# design.net
KiCad netlist of a schematic drawn in Altium Designer
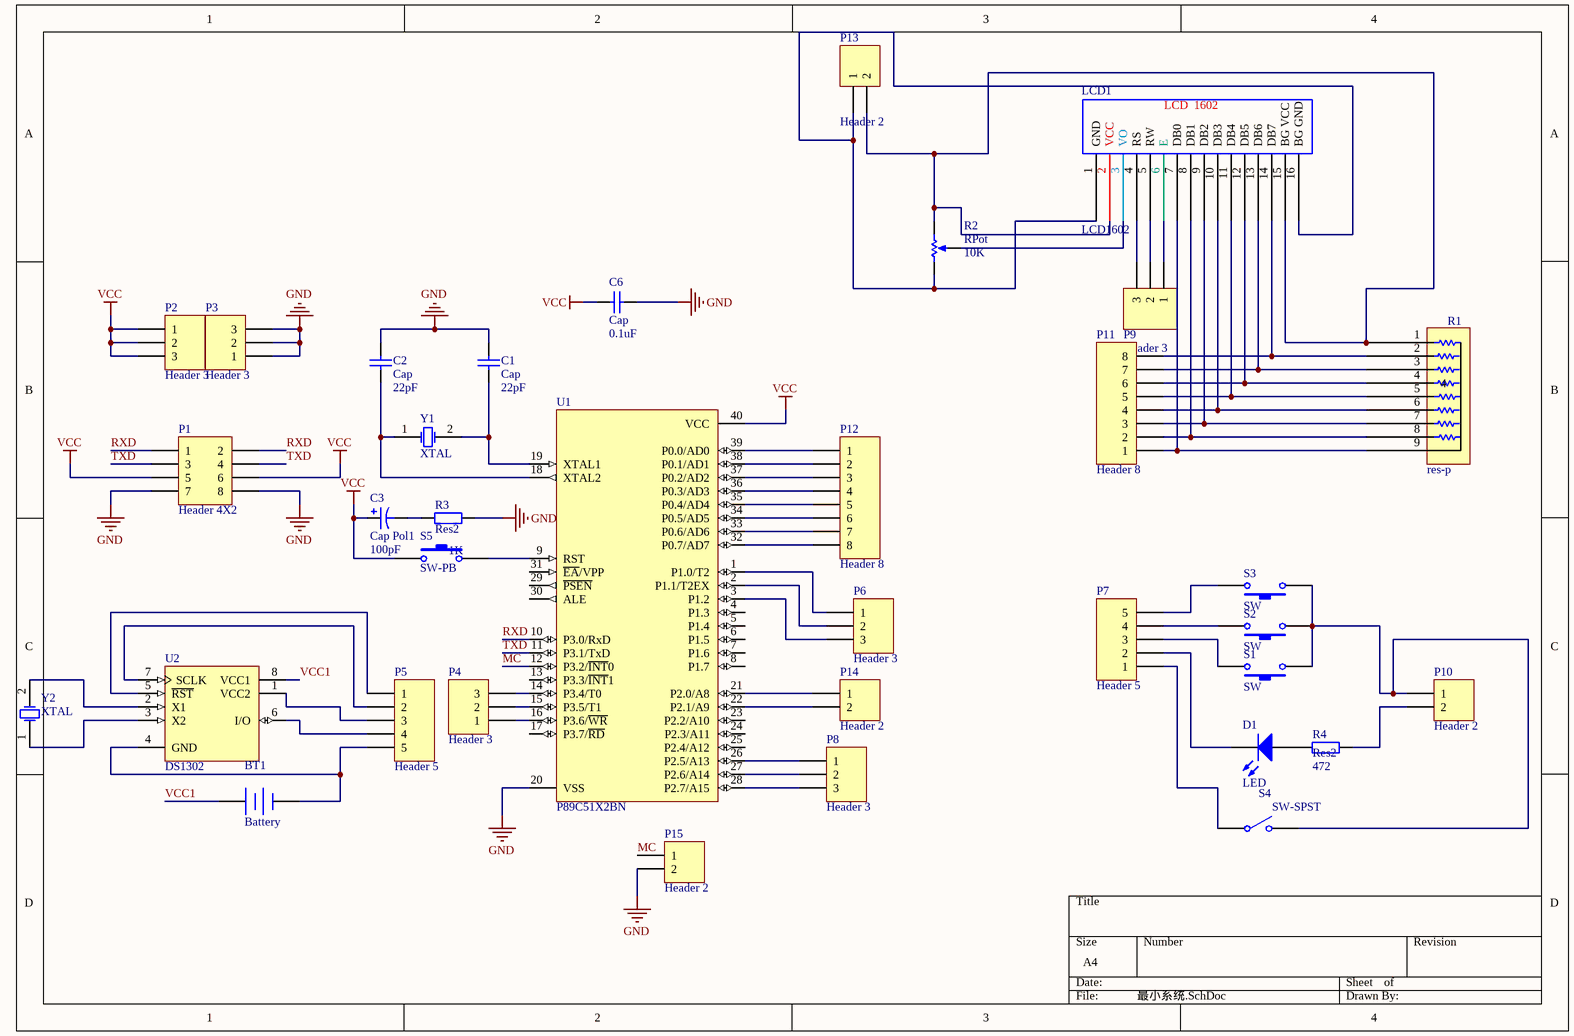
[diagram p0: 最小系统.SchDoc]

(export (version "E")
  (design (tool "Eeschema 10.0.6"))
  (components
    (comp (ref "BT1")
      (value "Battery")
      (footprint "BAT-2")
      (description "Multicell Battery")
      (fields (field (name "PUBLISHER") "Altium Limited"))
      (libsource (lib "Miscellaneous Devices") (part "Battery"))
    )
    (comp (ref "C1")
      (value "Cap")
      (footprint "CAPR2.54-5.1x3.2")
      (description "Capacitor")
      (fields (field (name "ALTIUM_VALUE") "22pF") (field (name "PUBLISHER") "Altium Limited"))
      (libsource (lib "Miscellaneous Devices") (part "Cap"))
    )
    (comp (ref "C2")
      (value "Cap")
      (footprint "CAPR2.54-5.1x3.2")
      (description "Capacitor")
      (fields (field (name "ALTIUM_VALUE") "22pF") (field (name "PUBLISHER") "Altium Limited"))
      (libsource (lib "Miscellaneous Devices") (part "Cap"))
    )
    (comp (ref "C3")
      (value "Cap Pol1")
      (footprint "CAPPR1.27-1.7x2.8")
      (description "Polarized Capacitor (Radial)")
      (fields (field (name "ALTIUM_VALUE") "100pF") (field (name "PUBLISHER") "Altium Limited"))
      (libsource (lib "Miscellaneous Devices") (part "Cap Pol1"))
    )
    (comp (ref "C6")
      (value "Cap")
      (footprint "RAD-0.3")
      (description "Capacitor")
      (fields (field (name "ALTIUM_VALUE") "0.1uF") (field (name "PUBLISHER") "Altium Limited"))
      (libsource (lib "Miscellaneous Devices") (part "Cap"))
    )
    (comp (ref "D1") (value "LED") (footprint "LED-1") (libsource (lib "我的集成库库") (part "LED")))
    (comp (ref "LCD1") (value "LCD1602") (footprint "1602LCD") (libsource (lib "MyInt_Lib") (part "LCD1602")))
    (comp (ref "P1")
      (value "Header 4X2")
      (footprint "HDR2X4")
      (description "Header, 4-Pin, Dual row")
      (fields (field (name "PUBLISHER") "Altium Limited"))
      (libsource (lib "Miscellaneous Connectors") (part "Header 4X2"))
    )
    (comp (ref "P2")
      (value "Header 3")
      (footprint "HDR1X3")
      (description "Header, 3-Pin")
      (fields (field (name "PUBLISHER") "Altium Limited"))
      (libsource (lib "Miscellaneous Connectors") (part "Header 3"))
    )
    (comp (ref "P3")
      (value "Header 3")
      (footprint "HDR1X3")
      (description "Header, 3-Pin")
      (fields (field (name "PUBLISHER") "Altium Limited"))
      (libsource (lib "") (part "Header 3_1"))
    )
    (comp (ref "P4")
      (value "Header 3")
      (footprint "HDR1X3")
      (description "Header, 3-Pin")
      (fields (field (name "PUBLISHER") "Altium Limited"))
      (libsource (lib "") (part "Header 3_1"))
    )
    (comp (ref "P5")
      (value "Header 5")
      (footprint "HDR1X5")
      (description "Header, 5-Pin")
      (fields (field (name "PUBLISHER") "Altium Limited"))
      (libsource (lib "") (part "Header 5_1"))
    )
    (comp (ref "P6")
      (value "Header 3")
      (footprint "HDR1X3")
      (description "Header, 3-Pin")
      (fields (field (name "PUBLISHER") "Altium Limited"))
      (libsource (lib "Miscellaneous Connectors") (part "Header 3"))
    )
    (comp (ref "P7")
      (value "Header 5")
      (footprint "HDR1X5")
      (description "Header, 5-Pin")
      (fields (field (name "PUBLISHER") "Altium Limited"))
      (libsource (lib "Miscellaneous Connectors") (part "Header 5"))
    )
    (comp (ref "P8")
      (value "Header 3")
      (footprint "HDR1X3")
      (description "Header, 3-Pin")
      (fields (field (name "PUBLISHER") "Altium Limited"))
      (libsource (lib "Miscellaneous Connectors") (part "Header 3"))
    )
    (comp (ref "P9")
      (value "Header 3")
      (footprint "HDR1X3")
      (description "Header, 3-Pin")
      (fields (field (name "PUBLISHER") "Altium Limited"))
      (libsource (lib "") (part "Header 3_2"))
    )
    (comp (ref "P10")
      (value "Header 2")
      (footprint "HDR1X2")
      (description "Header, 2-Pin")
      (fields (field (name "PUBLISHER") "Altium Limited"))
      (libsource (lib "") (part "Header 2_1"))
    )
    (comp (ref "P11")
      (value "Header 8")
      (footprint "HDR1X8")
      (description "Header, 8-Pin")
      (fields (field (name "PUBLISHER") "Altium Limited"))
      (libsource (lib "") (part "Header 8_1"))
    )
    (comp (ref "P12")
      (value "Header 8")
      (footprint "HDR1X8")
      (description "Header, 8-Pin")
      (fields (field (name "PUBLISHER") "Altium Limited"))
      (libsource (lib "Miscellaneous Connectors") (part "Header 8"))
    )
    (comp (ref "P13")
      (value "Header 2")
      (footprint "HDR1X2")
      (description "Header, 2-Pin")
      (fields (field (name "PUBLISHER") "Altium Limited"))
      (libsource (lib "Miscellaneous Connectors") (part "Header 2"))
    )
    (comp (ref "P14")
      (value "Header 2")
      (footprint "HDR1X2")
      (description "Header, 2-Pin")
      (fields (field (name "PUBLISHER") "Altium Limited"))
      (libsource (lib "") (part "Header 2_1"))
    )
    (comp (ref "P15")
      (value "Header 2")
      (footprint "HDR1X2")
      (description "Header, 2-Pin")
      (fields (field (name "PUBLISHER") "Altium Limited"))
      (libsource (lib "") (part "Header 2_1"))
    )
    (comp (ref "R1") (value "res-p") (footprint "HDR1X9") (libsource (lib "我的集成库库") (part "res-p")))
    (comp (ref "R2")
      (value "RPot")
      (footprint "VR5")
      (description "Potentiometer")
      (fields (field (name "ALTIUM_VALUE") "10K") (field (name "PUBLISHER") "Altium Limited"))
      (libsource (lib "Miscellaneous Devices") (part "RPot"))
    )
    (comp (ref "R3")
      (value "Res2")
      (footprint "AXIAL-0.4")
      (description "Resistor")
      (fields (field (name "ALTIUM_VALUE") "1K") (field (name "PUBLISHER") "Altium Limited"))
      (libsource (lib "Miscellaneous Devices") (part "Res2"))
    )
    (comp (ref "R4")
      (value "Res2")
      (footprint "AXIAL-0.4")
      (description "Resistor")
      (fields (field (name "ALTIUM_VALUE") "472") (field (name "PUBLISHER") "Altium Limited"))
      (libsource (lib "Miscellaneous Devices") (part "Res2"))
    )
    (comp (ref "S1") (value "SW") (footprint "SW/PB-V4/H7.1") (libsource (lib "我的集成库库") (part "SWITCH")))
    (comp (ref "S2") (value "SW") (footprint "SW/PB-V4/H7.1") (libsource (lib "我的集成库库") (part "SWITCH")))
    (comp (ref "S3") (value "SW") (footprint "SW/PB-V4/H7.1") (libsource (lib "我的集成库库") (part "SWITCH")))
    (comp (ref "S4")
      (value "SW-SPST")
      (footprint "SPST-2")
      (description "Single-Pole, Single-Throw Switch")
      (fields (field (name "PUBLISHER") "Altium Limited"))
      (libsource (lib "Miscellaneous Devices") (part "SW-SPST"))
    )
    (comp (ref "S5")
      (value "SW-PB")
      (footprint "SW/PB-V4/H7.1")
      (description "Switch")
      (fields (field (name "PUBLISHER") "Altium Limited"))
      (libsource (lib "Miscellaneous Devices") (part "SW-PB"))
    )
    (comp (ref "U1")
      (value "P89C51X2BN")
      (footprint "SOT129-1")
      (description "80C51 8-Bit Flash Microcontroller Family, 4 kB Flash")
      (fields (field (name "PUBLISHER") "Altium Limited"))
      (libsource (lib "Philips Microcontroller 8-Bit") (part "P89C51X2BN"))
    )
    (comp (ref "U2")
      (value "DS1302")
      (footprint "DIP8")
      (description "Trickle Charge Timekeeping Chip")
      (fields (field (name "PUBLISHER") "Altium Limited"))
      (libsource (lib "Dallas Peripheral Real Time Clock") (part "DS1302"))
    )
    (comp (ref "Y1")
      (value "XTAL")
      (footprint "BCY-W2/D3.1")
      (description "Crystal Oscillator")
      (fields (field (name "PUBLISHER") "Altium Limited"))
      (libsource (lib "Miscellaneous Devices") (part "XTAL"))
    )
    (comp (ref "Y2")
      (value "XTAL")
      (footprint "BCY-W2/D3.1")
      (description "Crystal Oscillator")
      (fields (field (name "PUBLISHER") "Altium Limited"))
      (libsource (lib "Miscellaneous Devices") (part "XTAL"))
    )
  )
  (nets
    (net (code "1") (name "/MC") (class "Default")
      (node (ref "P15") (pin "1") (pinfunction "1_1") (pintype "passive"))
      (node (ref "U1") (pin "12") (pinfunction "P3.2/~{INT}0_12") (pintype "bidirectional"))
    )
    (net (code "2") (name "/RXD") (class "Default")
      (node (ref "P1") (pin "1") (pinfunction "1_1") (pintype "passive"))
      (node (ref "P1") (pin "2") (pinfunction "2_2") (pintype "passive"))
      (node (ref "U1") (pin "10") (pinfunction "P3.0/RxD_10") (pintype "bidirectional"))
    )
    (net (code "3") (name "/TXD") (class "Default")
      (node (ref "P1") (pin "3") (pinfunction "3_3") (pintype "passive"))
      (node (ref "P1") (pin "4") (pinfunction "4_4") (pintype "passive"))
      (node (ref "U1") (pin "11") (pinfunction "P3.1/TxD_11") (pintype "bidirectional"))
    )
    (net (code "4") (name "/VCC1") (class "Default")
      (node (ref "BT1") (pin "1") (pinfunction "+_1") (pintype "passive"))
      (node (ref "U2") (pin "8") (pinfunction "VCC1_8") (pintype "power_in"))
    )
    (net (code "5") (name "GND") (class "Default")
      (node (ref "C1") (pin "2") (pinfunction "2_2") (pintype "passive"))
      (node (ref "C2") (pin "2") (pinfunction "2_2") (pintype "passive"))
      (node (ref "C6") (pin "2") (pinfunction "2_2") (pintype "passive"))
      (node (ref "P1") (pin "7") (pinfunction "7_7") (pintype "passive"))
      (node (ref "P1") (pin "8") (pinfunction "8_8") (pintype "passive"))
      (node (ref "P15") (pin "2") (pinfunction "2_2") (pintype "passive"))
      (node (ref "P3") (pin "1") (pinfunction "1_1") (pintype "passive"))
      (node (ref "P3") (pin "2") (pinfunction "2_2") (pintype "passive"))
      (node (ref "P3") (pin "3") (pinfunction "3_3") (pintype "passive"))
      (node (ref "R3") (pin "2") (pinfunction "2_2") (pintype "passive"))
      (node (ref "U1") (pin "20") (pinfunction "VSS_20") (pintype "power_in"))
    )
    (net (code "6") (name "Net-(BT1--)") (class "Default")
      (node (ref "BT1") (pin "2") (pinfunction "-_2") (pintype "passive"))
      (node (ref "P5") (pin "5") (pinfunction "5_5") (pintype "passive"))
      (node (ref "U2") (pin "4") (pinfunction "GND_4") (pintype "power_in"))
    )
    (net (code "7") (name "Net-(C3-Pad2)") (class "Default")
      (node (ref "C3") (pin "2") (pinfunction "2_2") (pintype "passive"))
      (node (ref "R3") (pin "1") (pinfunction "1_1") (pintype "passive"))
    )
    (net (code "8") (name "Net-(D1-A)") (class "Default")
      (node (ref "D1") (pin "1") (pinfunction "A_1") (pintype "passive"))
      (node (ref "R4") (pin "1") (pinfunction "1_1") (pintype "passive"))
    )
    (net (code "9") (name "Net-(D1-K)") (class "Default")
      (node (ref "D1") (pin "2") (pinfunction "K_2") (pintype "passive"))
      (node (ref "P7") (pin "2") (pinfunction "2_2") (pintype "passive"))
    )
    (net (code "10") (name "Net-(LCD1-BG_GND)") (class "Default")
      (node (ref "LCD1") (pin "1") (pinfunction "GND_1") (pintype "passive"))
      (node (ref "LCD1") (pin "16") (pinfunction "BG_GND_16") (pintype "passive"))
      (node (ref "P13") (pin "1") (pinfunction "1_1") (pintype "passive"))
      (node (ref "R2") (pin "1") (pinfunction "TOP_1") (pintype "passive"))
    )
    (net (code "11") (name "Net-(LCD1-BG_VCC)") (class "Default")
      (node (ref "LCD1") (pin "15") (pinfunction "BG_VCC_15") (pintype "passive"))
      (node (ref "LCD1") (pin "2") (pinfunction "VCC_2") (pintype "passive"))
      (node (ref "P13") (pin "2") (pinfunction "2_2") (pintype "passive"))
      (node (ref "R1") (pin "1") (pinfunction "1_1") (pintype "passive"))
      (node (ref "R2") (pin "2") (pinfunction "BOT_2") (pintype "passive"))
    )
    (net (code "12") (name "Net-(LCD1-DB0)") (class "Default")
      (node (ref "LCD1") (pin "7") (pinfunction "DB0_7") (pintype "passive"))
      (node (ref "P11") (pin "1") (pinfunction "1_1") (pintype "passive"))
      (node (ref "R1") (pin "9") (pinfunction "9_9") (pintype "passive"))
    )
    (net (code "13") (name "Net-(LCD1-DB1)") (class "Default")
      (node (ref "LCD1") (pin "8") (pinfunction "DB1_8") (pintype "passive"))
      (node (ref "P11") (pin "2") (pinfunction "2_2") (pintype "passive"))
      (node (ref "R1") (pin "8") (pinfunction "8_8") (pintype "passive"))
    )
    (net (code "14") (name "Net-(LCD1-DB2)") (class "Default")
      (node (ref "LCD1") (pin "9") (pinfunction "DB2_9") (pintype "passive"))
      (node (ref "P11") (pin "3") (pinfunction "3_3") (pintype "passive"))
      (node (ref "R1") (pin "7") (pinfunction "7_7") (pintype "passive"))
    )
    (net (code "15") (name "Net-(LCD1-DB3)") (class "Default")
      (node (ref "LCD1") (pin "10") (pinfunction "DB3_10") (pintype "passive"))
      (node (ref "P11") (pin "4") (pinfunction "4_4") (pintype "passive"))
      (node (ref "R1") (pin "6") (pinfunction "6_6") (pintype "passive"))
    )
    (net (code "16") (name "Net-(LCD1-DB4)") (class "Default")
      (node (ref "LCD1") (pin "11") (pinfunction "DB4_11") (pintype "passive"))
      (node (ref "P11") (pin "5") (pinfunction "5_5") (pintype "passive"))
      (node (ref "R1") (pin "5") (pinfunction "5_5") (pintype "passive"))
    )
    (net (code "17") (name "Net-(LCD1-DB5)") (class "Default")
      (node (ref "LCD1") (pin "12") (pinfunction "DB5_12") (pintype "passive"))
      (node (ref "P11") (pin "6") (pinfunction "6_6") (pintype "passive"))
      (node (ref "R1") (pin "4") (pinfunction "4_4") (pintype "passive"))
    )
    (net (code "18") (name "Net-(LCD1-DB6)") (class "Default")
      (node (ref "LCD1") (pin "13") (pinfunction "DB6_13") (pintype "passive"))
      (node (ref "P11") (pin "7") (pinfunction "7_7") (pintype "passive"))
      (node (ref "R1") (pin "3") (pinfunction "3_3") (pintype "passive"))
    )
    (net (code "19") (name "Net-(LCD1-DB7)") (class "Default")
      (node (ref "LCD1") (pin "14") (pinfunction "DB7_14") (pintype "passive"))
      (node (ref "P11") (pin "8") (pinfunction "8_8") (pintype "passive"))
      (node (ref "R1") (pin "2") (pinfunction "2_2") (pintype "passive"))
    )
    (net (code "20") (name "Net-(LCD1-E)") (class "Default")
      (node (ref "LCD1") (pin "6") (pinfunction "E_6") (pintype "passive"))
      (node (ref "P9") (pin "1") (pinfunction "1_1") (pintype "passive"))
    )
    (net (code "21") (name "Net-(LCD1-RS)") (class "Default")
      (node (ref "LCD1") (pin "4") (pinfunction "RS_4") (pintype "passive"))
      (node (ref "P9") (pin "3") (pinfunction "3_3") (pintype "passive"))
    )
    (net (code "22") (name "Net-(LCD1-RW)") (class "Default")
      (node (ref "LCD1") (pin "5") (pinfunction "RW_5") (pintype "passive"))
      (node (ref "P9") (pin "2") (pinfunction "2_2") (pintype "passive"))
    )
    (net (code "23") (name "Net-(LCD1-VO)") (class "Default")
      (node (ref "LCD1") (pin "3") (pinfunction "VO_3") (pintype "passive"))
      (node (ref "R2") (pin "3") (pinfunction "TAP_3") (pintype "passive"))
    )
    (net (code "24") (name "Net-(P7-Pad3)") (class "Default")
      (node (ref "P7") (pin "3") (pinfunction "3_3") (pintype "passive"))
      (node (ref "S1") (pin "2") (pinfunction "2_2") (pintype "passive"))
    )
    (net (code "25") (name "Net-(P7-Pad4)") (class "Default")
      (node (ref "P7") (pin "4") (pinfunction "4_4") (pintype "passive"))
      (node (ref "S2") (pin "2") (pinfunction "2_2") (pintype "passive"))
    )
    (net (code "26") (name "Net-(P7-Pad5)") (class "Default")
      (node (ref "P7") (pin "5") (pinfunction "5_5") (pintype "passive"))
      (node (ref "S3") (pin "2") (pinfunction "2_2") (pintype "passive"))
    )
    (net (code "27") (name "Net-(P10-Pad2)") (class "Default")
      (node (ref "P10") (pin "2") (pinfunction "2_2") (pintype "passive"))
      (node (ref "R4") (pin "2") (pinfunction "2_2") (pintype "passive"))
    )
    (net (code "28") (name "Net-(S4-COMMON)") (class "Default")
      (node (ref "P7") (pin "1") (pinfunction "1_1") (pintype "passive"))
      (node (ref "S4") (pin "1") (pinfunction "COMMON_1") (pintype "passive"))
    )
    (net (code "29") (name "Net-(S4-NO)") (class "Default")
      (node (ref "P10") (pin "1") (pinfunction "1_1") (pintype "passive"))
      (node (ref "S1") (pin "1") (pinfunction "1_1") (pintype "passive"))
      (node (ref "S2") (pin "1") (pinfunction "1_1") (pintype "passive"))
      (node (ref "S3") (pin "1") (pinfunction "1_1") (pintype "passive"))
      (node (ref "S4") (pin "2") (pinfunction "NO_2") (pintype "passive"))
    )
    (net (code "30") (name "Net-(U1-P0.0{slash}AD0)") (class "Default")
      (node (ref "P12") (pin "1") (pinfunction "1_1") (pintype "passive"))
      (node (ref "U1") (pin "39") (pinfunction "P0.0/AD0_39") (pintype "bidirectional"))
    )
    (net (code "31") (name "Net-(U1-P0.1{slash}AD1)") (class "Default")
      (node (ref "P12") (pin "2") (pinfunction "2_2") (pintype "passive"))
      (node (ref "U1") (pin "38") (pinfunction "P0.1/AD1_38") (pintype "bidirectional"))
    )
    (net (code "32") (name "Net-(U1-P0.2{slash}AD2)") (class "Default")
      (node (ref "P12") (pin "3") (pinfunction "3_3") (pintype "passive"))
      (node (ref "U1") (pin "37") (pinfunction "P0.2/AD2_37") (pintype "bidirectional"))
    )
    (net (code "33") (name "Net-(U1-P0.3{slash}AD3)") (class "Default")
      (node (ref "P12") (pin "4") (pinfunction "4_4") (pintype "passive"))
      (node (ref "U1") (pin "36") (pinfunction "P0.3/AD3_36") (pintype "bidirectional"))
    )
    (net (code "34") (name "Net-(U1-P0.4{slash}AD4)") (class "Default")
      (node (ref "P12") (pin "5") (pinfunction "5_5") (pintype "passive"))
      (node (ref "U1") (pin "35") (pinfunction "P0.4/AD4_35") (pintype "bidirectional"))
    )
    (net (code "35") (name "Net-(U1-P0.5{slash}AD5)") (class "Default")
      (node (ref "P12") (pin "6") (pinfunction "6_6") (pintype "passive"))
      (node (ref "U1") (pin "34") (pinfunction "P0.5/AD5_34") (pintype "bidirectional"))
    )
    (net (code "36") (name "Net-(U1-P0.6{slash}AD6)") (class "Default")
      (node (ref "P12") (pin "7") (pinfunction "7_7") (pintype "passive"))
      (node (ref "U1") (pin "33") (pinfunction "P0.6/AD6_33") (pintype "bidirectional"))
    )
    (net (code "37") (name "Net-(U1-P0.7{slash}AD7)") (class "Default")
      (node (ref "P12") (pin "8") (pinfunction "8_8") (pintype "passive"))
      (node (ref "U1") (pin "32") (pinfunction "P0.7/AD7_32") (pintype "bidirectional"))
    )
    (net (code "38") (name "Net-(U1-P1.0{slash}T2)") (class "Default")
      (node (ref "P6") (pin "1") (pinfunction "1_1") (pintype "passive"))
      (node (ref "U1") (pin "1") (pinfunction "P1.0/T2_1") (pintype "bidirectional"))
    )
    (net (code "39") (name "Net-(U1-P1.1{slash}T2EX)") (class "Default")
      (node (ref "P6") (pin "2") (pinfunction "2_2") (pintype "passive"))
      (node (ref "U1") (pin "2") (pinfunction "P1.1/T2EX_2") (pintype "bidirectional"))
    )
    (net (code "40") (name "Net-(U1-P1.2)") (class "Default")
      (node (ref "P6") (pin "3") (pinfunction "3_3") (pintype "passive"))
      (node (ref "U1") (pin "3") (pinfunction "P1.2_3") (pintype "bidirectional"))
    )
    (net (code "41") (name "Net-(U1-P2.0{slash}A8)") (class "Default")
      (node (ref "P14") (pin "1") (pinfunction "1_1") (pintype "passive"))
      (node (ref "U1") (pin "21") (pinfunction "P2.0/A8_21") (pintype "bidirectional"))
    )
    (net (code "42") (name "Net-(U1-P2.1{slash}A9)") (class "Default")
      (node (ref "P14") (pin "2") (pinfunction "2_2") (pintype "passive"))
      (node (ref "U1") (pin "22") (pinfunction "P2.1/A9_22") (pintype "bidirectional"))
    )
    (net (code "43") (name "Net-(U1-P2.5{slash}A13)") (class "Default")
      (node (ref "P8") (pin "1") (pinfunction "1_1") (pintype "passive"))
      (node (ref "U1") (pin "26") (pinfunction "P2.5/A13_26") (pintype "bidirectional"))
    )
    (net (code "44") (name "Net-(U1-P2.6{slash}A14)") (class "Default")
      (node (ref "P8") (pin "2") (pinfunction "2_2") (pintype "passive"))
      (node (ref "U1") (pin "27") (pinfunction "P2.6/A14_27") (pintype "bidirectional"))
    )
    (net (code "45") (name "Net-(U1-P2.7{slash}A15)") (class "Default")
      (node (ref "P8") (pin "3") (pinfunction "3_3") (pintype "passive"))
      (node (ref "U1") (pin "28") (pinfunction "P2.7/A15_28") (pintype "bidirectional"))
    )
    (net (code "46") (name "Net-(U1-P3.4{slash}T0)") (class "Default")
      (node (ref "P4") (pin "3") (pinfunction "3_3") (pintype "passive"))
      (node (ref "U1") (pin "14") (pinfunction "P3.4/T0_14") (pintype "bidirectional"))
    )
    (net (code "47") (name "Net-(U1-P3.5{slash}T1)") (class "Default")
      (node (ref "P4") (pin "2") (pinfunction "2_2") (pintype "passive"))
      (node (ref "U1") (pin "15") (pinfunction "P3.5/T1_15") (pintype "bidirectional"))
    )
    (net (code "48") (name "Net-(U1-P3.6{slash}~{WR})") (class "Default")
      (node (ref "P4") (pin "1") (pinfunction "1_1") (pintype "passive"))
      (node (ref "U1") (pin "16") (pinfunction "P3.6/~{WR}_16") (pintype "bidirectional"))
    )
    (net (code "49") (name "Net-(U1-RST)") (class "Default")
      (node (ref "S5") (pin "2") (pinfunction "2_2") (pintype "passive"))
      (node (ref "U1") (pin "9") (pinfunction "RST_9") (pintype "input"))
    )
    (net (code "50") (name "Net-(U1-XTAL1)") (class "Default")
      (node (ref "C1") (pin "1") (pinfunction "1_1") (pintype "passive"))
      (node (ref "U1") (pin "19") (pinfunction "XTAL1_19") (pintype "input"))
      (node (ref "Y1") (pin "2") (pinfunction "OSC2_2") (pintype "passive"))
    )
    (net (code "51") (name "Net-(U1-XTAL2)") (class "Default")
      (node (ref "C2") (pin "1") (pinfunction "1_1") (pintype "passive"))
      (node (ref "U1") (pin "18") (pinfunction "XTAL2_18") (pintype "output"))
      (node (ref "Y1") (pin "1") (pinfunction "OSC1_1") (pintype "passive"))
    )
    (net (code "52") (name "Net-(U2-I{slash}O)") (class "Default")
      (node (ref "P5") (pin "4") (pinfunction "4_4") (pintype "passive"))
      (node (ref "U2") (pin "6") (pinfunction "I/O_6") (pintype "bidirectional"))
    )
    (net (code "53") (name "Net-(U2-SCLK)") (class "Default")
      (node (ref "P5") (pin "2") (pinfunction "2_2") (pintype "passive"))
      (node (ref "U2") (pin "7") (pinfunction "SCLK_7") (pintype "input"))
    )
    (net (code "54") (name "Net-(U2-VCC2)") (class "Default")
      (node (ref "P5") (pin "3") (pinfunction "3_3") (pintype "passive"))
      (node (ref "U2") (pin "1") (pinfunction "VCC2_1") (pintype "power_in"))
    )
    (net (code "55") (name "Net-(U2-X1)") (class "Default")
      (node (ref "U2") (pin "2") (pinfunction "X1_2") (pintype "input"))
      (node (ref "Y2") (pin "2") (pinfunction "OSC2_2") (pintype "passive"))
    )
    (net (code "56") (name "Net-(U2-X2)") (class "Default")
      (node (ref "U2") (pin "3") (pinfunction "X2_3") (pintype "input"))
      (node (ref "Y2") (pin "1") (pinfunction "OSC1_1") (pintype "passive"))
    )
    (net (code "57") (name "Net-(U2-~{RST})") (class "Default")
      (node (ref "P5") (pin "1") (pinfunction "1_1") (pintype "passive"))
      (node (ref "U2") (pin "5") (pinfunction "~{RST}_5") (pintype "input"))
    )
    (net (code "58") (name "VCC") (class "Default")
      (node (ref "C3") (pin "1") (pinfunction "1_1") (pintype "passive"))
      (node (ref "C6") (pin "1") (pinfunction "1_1") (pintype "passive"))
      (node (ref "P1") (pin "5") (pinfunction "5_5") (pintype "passive"))
      (node (ref "P1") (pin "6") (pinfunction "6_6") (pintype "passive"))
      (node (ref "P2") (pin "1") (pinfunction "1_1") (pintype "passive"))
      (node (ref "P2") (pin "2") (pinfunction "2_2") (pintype "passive"))
      (node (ref "P2") (pin "3") (pinfunction "3_3") (pintype "passive"))
      (node (ref "S5") (pin "1") (pinfunction "1_1") (pintype "passive"))
      (node (ref "U1") (pin "40") (pinfunction "VCC_40") (pintype "power_in"))
    )
    (net (code "59") (name "unconnected-(U1-ALE-Pad30)") (class "Default")
      (node (ref "U1") (pin "30") (pinfunction "ALE_30") (pintype "output"))
    )
    (net (code "60") (name "unconnected-(U1-P1.3-Pad4)") (class "Default")
      (node (ref "U1") (pin "4") (pinfunction "P1.3_4") (pintype "bidirectional"))
    )
    (net (code "61") (name "unconnected-(U1-P1.4-Pad5)") (class "Default")
      (node (ref "U1") (pin "5") (pinfunction "P1.4_5") (pintype "bidirectional"))
    )
    (net (code "62") (name "unconnected-(U1-P1.5-Pad6)") (class "Default")
      (node (ref "U1") (pin "6") (pinfunction "P1.5_6") (pintype "bidirectional"))
    )
    (net (code "63") (name "unconnected-(U1-P1.6-Pad7)") (class "Default")
      (node (ref "U1") (pin "7") (pinfunction "P1.6_7") (pintype "bidirectional"))
    )
    (net (code "64") (name "unconnected-(U1-P1.7-Pad8)") (class "Default")
      (node (ref "U1") (pin "8") (pinfunction "P1.7_8") (pintype "bidirectional"))
    )
    (net (code "65") (name "unconnected-(U1-P2.2{slash}A10-Pad23)") (class "Default")
      (node (ref "U1") (pin "23") (pinfunction "P2.2/A10_23") (pintype "bidirectional"))
    )
    (net (code "66") (name "unconnected-(U1-P2.3{slash}A11-Pad24)") (class "Default")
      (node (ref "U1") (pin "24") (pinfunction "P2.3/A11_24") (pintype "bidirectional"))
    )
    (net (code "67") (name "unconnected-(U1-P2.4{slash}A12-Pad25)") (class "Default")
      (node (ref "U1") (pin "25") (pinfunction "P2.4/A12_25") (pintype "bidirectional"))
    )
    (net (code "68") (name "unconnected-(U1-P3.3{slash}~{INT}1-Pad13)") (class "Default")
      (node (ref "U1") (pin "13") (pinfunction "P3.3/~{INT}1_13") (pintype "bidirectional"))
    )
    (net (code "69") (name "unconnected-(U1-P3.7{slash}~{RD}-Pad17)") (class "Default")
      (node (ref "U1") (pin "17") (pinfunction "P3.7/~{RD}_17") (pintype "bidirectional"))
    )
    (net (code "70") (name "unconnected-(U1-~{EA}{slash}VPP-Pad31)") (class "Default")
      (node (ref "U1") (pin "31") (pinfunction "~{EA}/VPP_31") (pintype "input"))
    )
    (net (code "71") (name "unconnected-(U1-~{PSEN}-Pad29)") (class "Default")
      (node (ref "U1") (pin "29") (pinfunction "~{PSEN}_29") (pintype "output"))
    )
  )
)
